# oled_array_v1.net
KiCad netlist of a schematic drawn in EAGLE
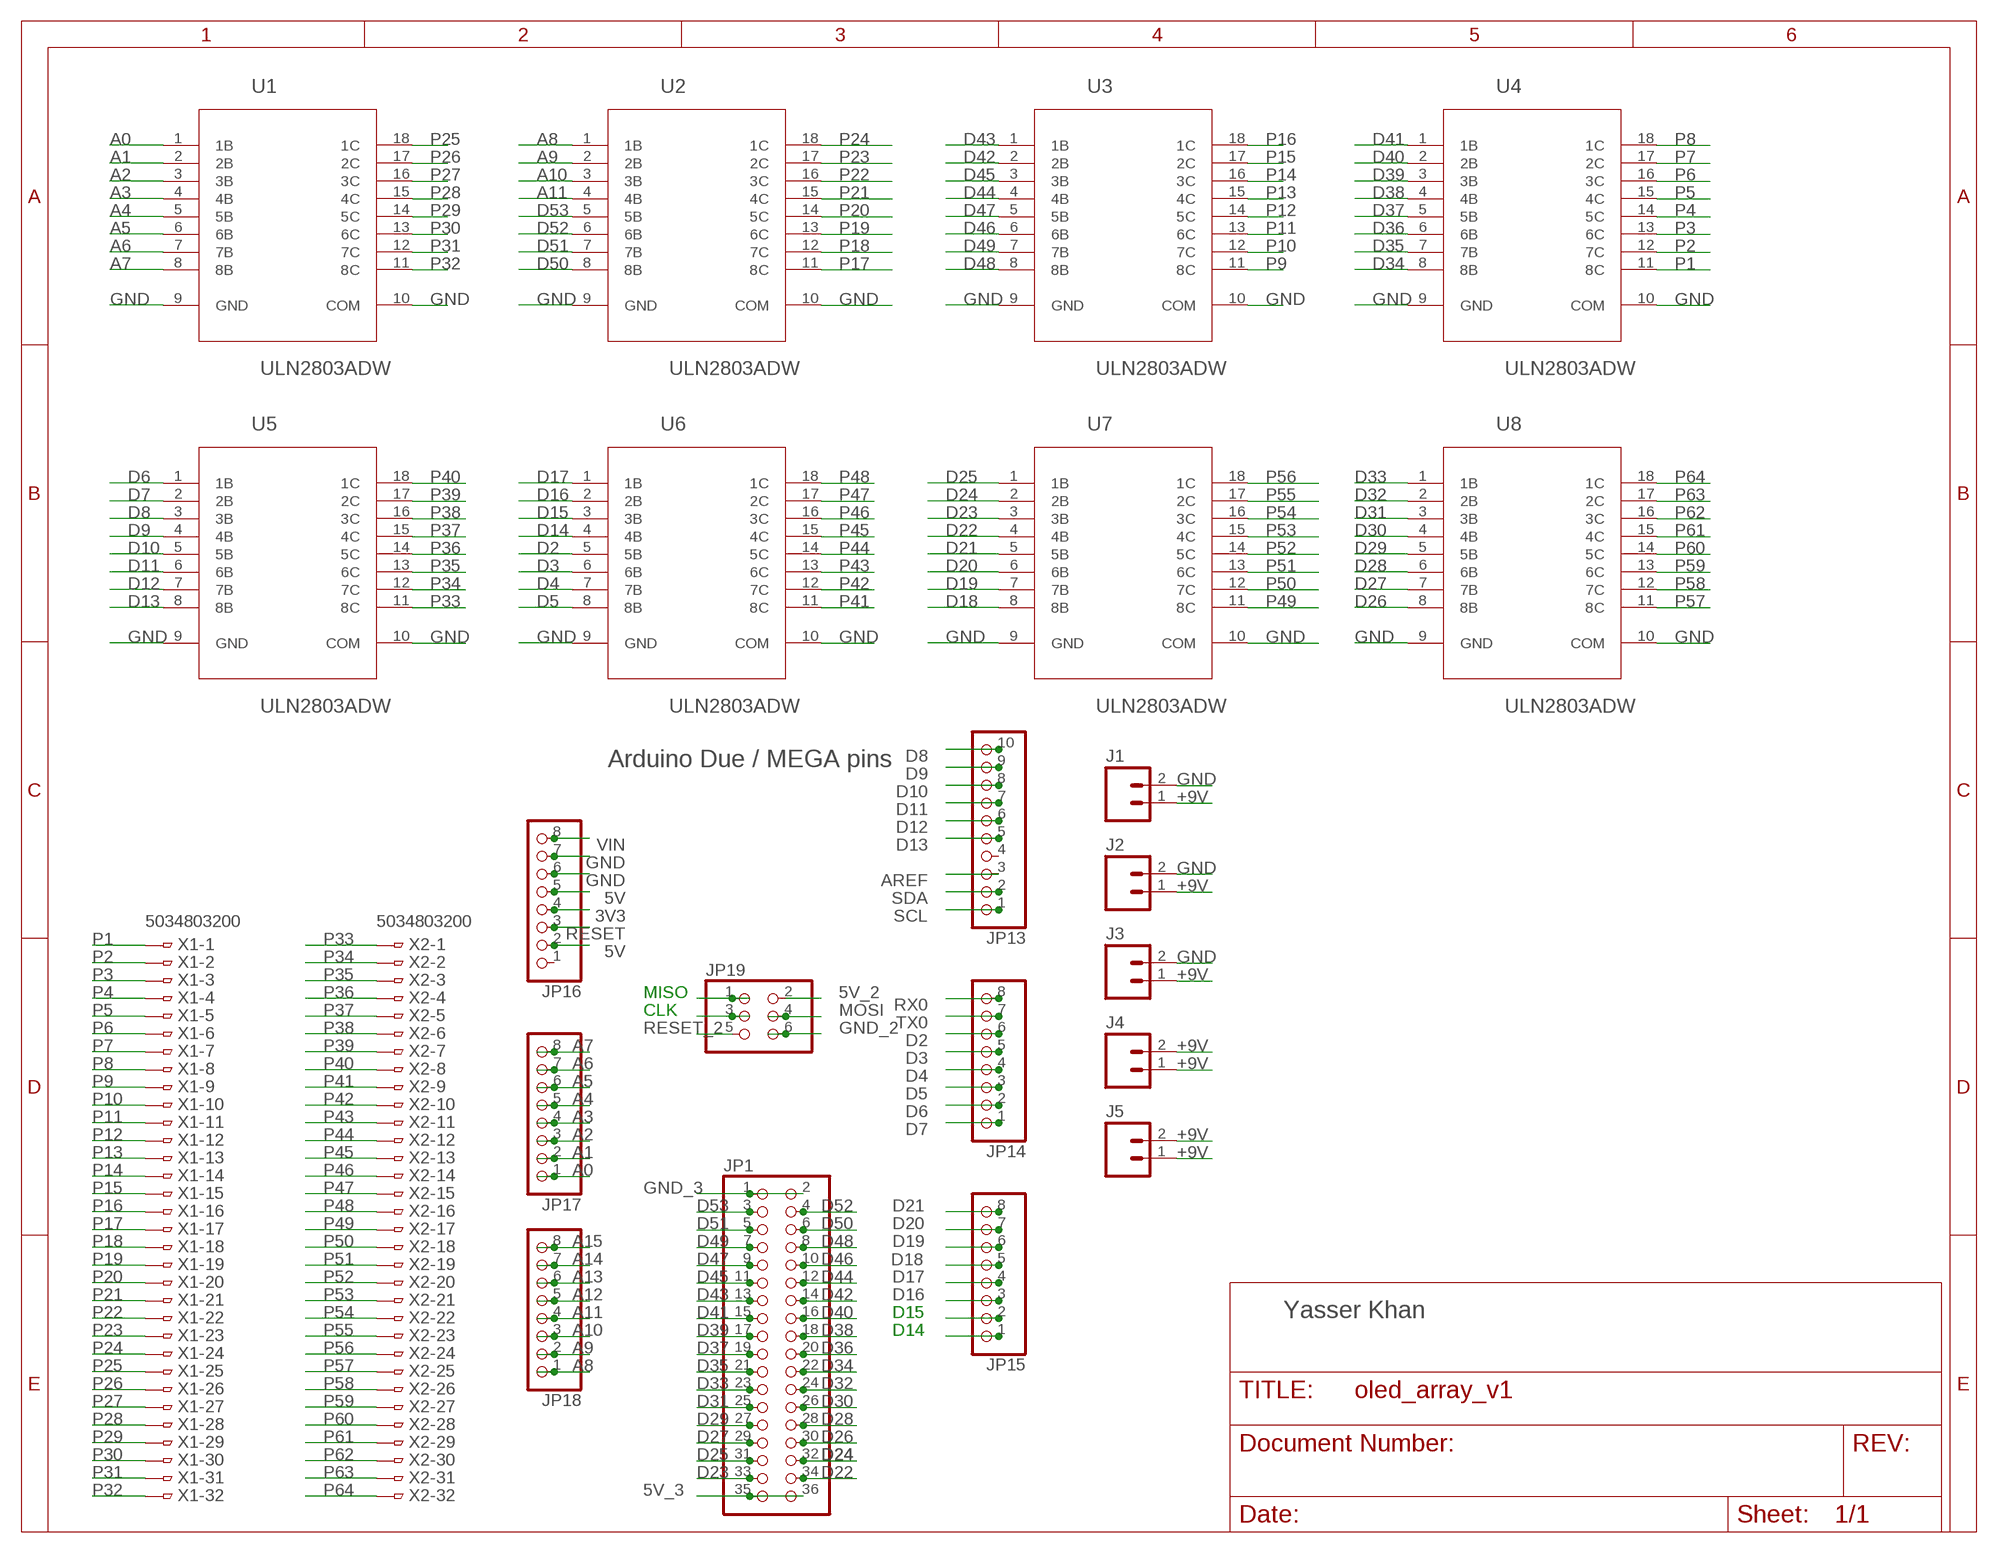
[diagram p0: schematic, sheet 1]

(export (version "E")
  (design (tool "Eeschema 10.0.6"))
  (components
    (comp (ref "J1")
      (value "M02PTH")
      (footprint "eagle-import:1X02")
      (libsource (lib "eagle-import") (part "M02PTH"))
    )
    (comp (ref "J2")
      (value "M02PTH")
      (footprint "eagle-import:1X02")
      (libsource (lib "eagle-import") (part "M02PTH"))
    )
    (comp (ref "J3")
      (value "M02PTH")
      (footprint "eagle-import:1X02")
      (libsource (lib "eagle-import") (part "M02PTH"))
    )
    (comp (ref "J4")
      (value "M02PTH")
      (footprint "eagle-import:1X02")
      (libsource (lib "eagle-import") (part "M02PTH"))
    )
    (comp (ref "J5")
      (value "M02PTH")
      (footprint "eagle-import:1X02")
      (libsource (lib "eagle-import") (part "M02PTH"))
    )
    (comp (ref "JP1")
      (value "PINHD-2X18")
      (footprint "eagle-import:2X18")
      (libsource (lib "eagle-import") (part "PINHD-2X18"))
    )
    (comp (ref "JP13")
      (value "PINHD-1X10")
      (footprint "eagle-import:1X10")
      (libsource (lib "eagle-import") (part "PINHD-1X10"))
    )
    (comp (ref "JP14")
      (value "PINHD-1X8")
      (footprint "eagle-import:1X08")
      (libsource (lib "eagle-import") (part "PINHD-1X8"))
    )
    (comp (ref "JP15")
      (value "PINHD-1X8")
      (footprint "eagle-import:1X08")
      (libsource (lib "eagle-import") (part "PINHD-1X8"))
    )
    (comp (ref "JP16")
      (value "PINHD-1X8")
      (footprint "eagle-import:1X08")
      (libsource (lib "eagle-import") (part "PINHD-1X8"))
    )
    (comp (ref "JP17")
      (value "PINHD-1X8")
      (footprint "eagle-import:1X08")
      (libsource (lib "eagle-import") (part "PINHD-1X8"))
    )
    (comp (ref "JP18")
      (value "PINHD-1X8")
      (footprint "eagle-import:1X08")
      (libsource (lib "eagle-import") (part "PINHD-1X8"))
    )
    (comp (ref "JP19")
      (value "PINHD-2X3")
      (footprint "eagle-import:2X03")
      (libsource (lib "eagle-import") (part "PINHD-2X3"))
    )
    (comp (ref "U1")
      (value "ULN2803ADW")
      (footprint "eagle-import:SOIC127P1030X265-18N")
      (libsource (lib "eagle-import") (part "ULN2803ADW"))
    )
    (comp (ref "U2")
      (value "ULN2803ADW")
      (footprint "eagle-import:SOIC127P1030X265-18N")
      (libsource (lib "eagle-import") (part "ULN2803ADW"))
    )
    (comp (ref "U3")
      (value "ULN2803ADW")
      (footprint "eagle-import:SOIC127P1030X265-18N")
      (libsource (lib "eagle-import") (part "ULN2803ADW"))
    )
    (comp (ref "U4")
      (value "ULN2803ADW")
      (footprint "eagle-import:SOIC127P1030X265-18N")
      (libsource (lib "eagle-import") (part "ULN2803ADW"))
    )
    (comp (ref "U5")
      (value "ULN2803ADW")
      (footprint "eagle-import:SOIC127P1030X265-18N")
      (libsource (lib "eagle-import") (part "ULN2803ADW"))
    )
    (comp (ref "U6")
      (value "ULN2803ADW")
      (footprint "eagle-import:SOIC127P1030X265-18N")
      (libsource (lib "eagle-import") (part "ULN2803ADW"))
    )
    (comp (ref "U7")
      (value "ULN2803ADW")
      (footprint "eagle-import:SOIC127P1030X265-18N")
      (libsource (lib "eagle-import") (part "ULN2803ADW"))
    )
    (comp (ref "U8")
      (value "ULN2803ADW")
      (footprint "eagle-import:SOIC127P1030X265-18N")
      (libsource (lib "eagle-import") (part "ULN2803ADW"))
    )
    (comp (ref "X1")
      (value "5034803200")
      (footprint "eagle-import:5034803200")
      (libsource (lib "eagle-import") (part "5034803200"))
    )
    (comp (ref "X2")
      (value "5034803200")
      (footprint "eagle-import:5034803200")
      (libsource (lib "eagle-import") (part "5034803200"))
    )
  )
  (nets
    (net (code "1") (name "/+9V") (class "Default")
      (node (ref "J1") (pin "1") (pinfunction "1_1") (pintype "passive"))
      (node (ref "J2") (pin "1") (pinfunction "1_1") (pintype "passive"))
      (node (ref "J3") (pin "1") (pinfunction "1_1") (pintype "passive"))
      (node (ref "J4") (pin "1") (pinfunction "1_1") (pintype "passive"))
      (node (ref "J4") (pin "2") (pinfunction "2_2") (pintype "passive"))
      (node (ref "J5") (pin "1") (pinfunction "1_1") (pintype "passive"))
      (node (ref "J5") (pin "2") (pinfunction "2_2") (pintype "passive"))
    )
    (net (code "2") (name "/3V3") (class "Default")
      (node (ref "JP16") (pin "4") (pinfunction "4_4") (pintype "passive"))
    )
    (net (code "3") (name "/5V") (class "Default")
      (node (ref "JP16") (pin "2") (pinfunction "2_2") (pintype "passive"))
      (node (ref "JP16") (pin "5") (pinfunction "5_5") (pintype "passive"))
    )
    (net (code "4") (name "/5V_2") (class "Default")
      (node (ref "JP19") (pin "2") (pinfunction "2_2") (pintype "passive"))
    )
    (net (code "5") (name "/5V_3") (class "Default")
      (node (ref "JP1") (pin "35") (pinfunction "35_35") (pintype "passive"))
      (node (ref "JP1") (pin "36") (pinfunction "36_36") (pintype "passive"))
    )
    (net (code "6") (name "/A0") (class "Default")
      (node (ref "JP17") (pin "1") (pinfunction "1_1") (pintype "passive"))
      (node (ref "U1") (pin "1") (pinfunction "1B_1") (pintype "input"))
    )
    (net (code "7") (name "/A1") (class "Default")
      (node (ref "JP17") (pin "2") (pinfunction "2_2") (pintype "passive"))
      (node (ref "U1") (pin "2") (pinfunction "2B_2") (pintype "input"))
    )
    (net (code "8") (name "/A2") (class "Default")
      (node (ref "JP17") (pin "3") (pinfunction "3_3") (pintype "passive"))
      (node (ref "U1") (pin "3") (pinfunction "3B_3") (pintype "input"))
    )
    (net (code "9") (name "/A3") (class "Default")
      (node (ref "JP17") (pin "4") (pinfunction "4_4") (pintype "passive"))
      (node (ref "U1") (pin "4") (pinfunction "4B_4") (pintype "input"))
    )
    (net (code "10") (name "/A4") (class "Default")
      (node (ref "JP17") (pin "5") (pinfunction "5_5") (pintype "passive"))
      (node (ref "U1") (pin "5") (pinfunction "5B_5") (pintype "input"))
    )
    (net (code "11") (name "/A5") (class "Default")
      (node (ref "JP17") (pin "6") (pinfunction "6_6") (pintype "passive"))
      (node (ref "U1") (pin "6") (pinfunction "6B_6") (pintype "input"))
    )
    (net (code "12") (name "/A6") (class "Default")
      (node (ref "JP17") (pin "7") (pinfunction "7_7") (pintype "passive"))
      (node (ref "U1") (pin "7") (pinfunction "7B_7") (pintype "input"))
    )
    (net (code "13") (name "/A7") (class "Default")
      (node (ref "JP17") (pin "8") (pinfunction "8_8") (pintype "passive"))
      (node (ref "U1") (pin "8") (pinfunction "8B_8") (pintype "input"))
    )
    (net (code "14") (name "/A8") (class "Default")
      (node (ref "JP18") (pin "1") (pinfunction "1_1") (pintype "passive"))
      (node (ref "U2") (pin "1") (pinfunction "1B_1") (pintype "input"))
    )
    (net (code "15") (name "/A9") (class "Default")
      (node (ref "JP18") (pin "2") (pinfunction "2_2") (pintype "passive"))
      (node (ref "U2") (pin "2") (pinfunction "2B_2") (pintype "input"))
    )
    (net (code "16") (name "/A10") (class "Default")
      (node (ref "JP18") (pin "3") (pinfunction "3_3") (pintype "passive"))
      (node (ref "U2") (pin "3") (pinfunction "3B_3") (pintype "input"))
    )
    (net (code "17") (name "/A11") (class "Default")
      (node (ref "JP18") (pin "4") (pinfunction "4_4") (pintype "passive"))
      (node (ref "U2") (pin "4") (pinfunction "4B_4") (pintype "input"))
    )
    (net (code "18") (name "/A12") (class "Default")
      (node (ref "JP18") (pin "5") (pinfunction "5_5") (pintype "passive"))
    )
    (net (code "19") (name "/A13") (class "Default")
      (node (ref "JP18") (pin "6") (pinfunction "6_6") (pintype "passive"))
    )
    (net (code "20") (name "/A14") (class "Default")
      (node (ref "JP18") (pin "7") (pinfunction "7_7") (pintype "passive"))
    )
    (net (code "21") (name "/A15") (class "Default")
      (node (ref "JP18") (pin "8") (pinfunction "8_8") (pintype "passive"))
    )
    (net (code "22") (name "/AREF") (class "Default")
      (node (ref "JP13") (pin "3") (pinfunction "3_3") (pintype "passive"))
    )
    (net (code "23") (name "/CLK") (class "Default")
      (node (ref "JP19") (pin "3") (pinfunction "3_3") (pintype "passive"))
    )
    (net (code "24") (name "/D2") (class "Default")
      (node (ref "JP14") (pin "6") (pinfunction "6_6") (pintype "passive"))
      (node (ref "U6") (pin "5") (pinfunction "5B_5") (pintype "input"))
    )
    (net (code "25") (name "/D3") (class "Default")
      (node (ref "JP14") (pin "5") (pinfunction "5_5") (pintype "passive"))
      (node (ref "U6") (pin "6") (pinfunction "6B_6") (pintype "input"))
    )
    (net (code "26") (name "/D4") (class "Default")
      (node (ref "JP14") (pin "4") (pinfunction "4_4") (pintype "passive"))
      (node (ref "U6") (pin "7") (pinfunction "7B_7") (pintype "input"))
    )
    (net (code "27") (name "/D5") (class "Default")
      (node (ref "JP14") (pin "3") (pinfunction "3_3") (pintype "passive"))
      (node (ref "U6") (pin "8") (pinfunction "8B_8") (pintype "input"))
    )
    (net (code "28") (name "/D6") (class "Default")
      (node (ref "JP14") (pin "2") (pinfunction "2_2") (pintype "passive"))
      (node (ref "U5") (pin "1") (pinfunction "1B_1") (pintype "input"))
    )
    (net (code "29") (name "/D7") (class "Default")
      (node (ref "JP14") (pin "1") (pinfunction "1_1") (pintype "passive"))
      (node (ref "U5") (pin "2") (pinfunction "2B_2") (pintype "input"))
    )
    (net (code "30") (name "/D8") (class "Default")
      (node (ref "JP13") (pin "10") (pinfunction "10_10") (pintype "passive"))
      (node (ref "U5") (pin "3") (pinfunction "3B_3") (pintype "input"))
    )
    (net (code "31") (name "/D9") (class "Default")
      (node (ref "JP13") (pin "9") (pinfunction "9_9") (pintype "passive"))
      (node (ref "U5") (pin "4") (pinfunction "4B_4") (pintype "input"))
    )
    (net (code "32") (name "/D10") (class "Default")
      (node (ref "JP13") (pin "8") (pinfunction "8_8") (pintype "passive"))
      (node (ref "U5") (pin "5") (pinfunction "5B_5") (pintype "input"))
    )
    (net (code "33") (name "/D11") (class "Default")
      (node (ref "JP13") (pin "7") (pinfunction "7_7") (pintype "passive"))
      (node (ref "U5") (pin "6") (pinfunction "6B_6") (pintype "input"))
    )
    (net (code "34") (name "/D12") (class "Default")
      (node (ref "JP13") (pin "6") (pinfunction "6_6") (pintype "passive"))
      (node (ref "U5") (pin "7") (pinfunction "7B_7") (pintype "input"))
    )
    (net (code "35") (name "/D13") (class "Default")
      (node (ref "JP13") (pin "5") (pinfunction "5_5") (pintype "passive"))
      (node (ref "U5") (pin "8") (pinfunction "8B_8") (pintype "input"))
    )
    (net (code "36") (name "/D14") (class "Default")
      (node (ref "JP15") (pin "1") (pinfunction "1_1") (pintype "passive"))
      (node (ref "U6") (pin "4") (pinfunction "4B_4") (pintype "input"))
    )
    (net (code "37") (name "/D15") (class "Default")
      (node (ref "JP15") (pin "2") (pinfunction "2_2") (pintype "passive"))
      (node (ref "U6") (pin "3") (pinfunction "3B_3") (pintype "input"))
    )
    (net (code "38") (name "/D16") (class "Default")
      (node (ref "JP15") (pin "3") (pinfunction "3_3") (pintype "passive"))
      (node (ref "U6") (pin "2") (pinfunction "2B_2") (pintype "input"))
    )
    (net (code "39") (name "/D17") (class "Default")
      (node (ref "JP15") (pin "4") (pinfunction "4_4") (pintype "passive"))
      (node (ref "U6") (pin "1") (pinfunction "1B_1") (pintype "input"))
    )
    (net (code "40") (name "/D18") (class "Default")
      (node (ref "JP15") (pin "5") (pinfunction "5_5") (pintype "passive"))
      (node (ref "U7") (pin "8") (pinfunction "8B_8") (pintype "input"))
    )
    (net (code "41") (name "/D19") (class "Default")
      (node (ref "JP15") (pin "6") (pinfunction "6_6") (pintype "passive"))
      (node (ref "U7") (pin "7") (pinfunction "7B_7") (pintype "input"))
    )
    (net (code "42") (name "/D20") (class "Default")
      (node (ref "JP15") (pin "7") (pinfunction "7_7") (pintype "passive"))
      (node (ref "U7") (pin "6") (pinfunction "6B_6") (pintype "input"))
    )
    (net (code "43") (name "/D21") (class "Default")
      (node (ref "JP15") (pin "8") (pinfunction "8_8") (pintype "passive"))
      (node (ref "U7") (pin "5") (pinfunction "5B_5") (pintype "input"))
    )
    (net (code "44") (name "/D22") (class "Default")
      (node (ref "JP1") (pin "34") (pinfunction "34_34") (pintype "passive"))
      (node (ref "U7") (pin "4") (pinfunction "4B_4") (pintype "input"))
    )
    (net (code "45") (name "/D23") (class "Default")
      (node (ref "JP1") (pin "33") (pinfunction "33_33") (pintype "passive"))
      (node (ref "U7") (pin "3") (pinfunction "3B_3") (pintype "input"))
    )
    (net (code "46") (name "/D24") (class "Default")
      (node (ref "JP1") (pin "32") (pinfunction "32_32") (pintype "passive"))
      (node (ref "U7") (pin "2") (pinfunction "2B_2") (pintype "input"))
    )
    (net (code "47") (name "/D25") (class "Default")
      (node (ref "JP1") (pin "31") (pinfunction "31_31") (pintype "passive"))
      (node (ref "U7") (pin "1") (pinfunction "1B_1") (pintype "input"))
    )
    (net (code "48") (name "/D26") (class "Default")
      (node (ref "JP1") (pin "30") (pinfunction "30_30") (pintype "passive"))
      (node (ref "U8") (pin "8") (pinfunction "8B_8") (pintype "input"))
    )
    (net (code "49") (name "/D27") (class "Default")
      (node (ref "JP1") (pin "29") (pinfunction "29_29") (pintype "passive"))
      (node (ref "U8") (pin "7") (pinfunction "7B_7") (pintype "input"))
    )
    (net (code "50") (name "/D28") (class "Default")
      (node (ref "JP1") (pin "28") (pinfunction "28_28") (pintype "passive"))
      (node (ref "U8") (pin "6") (pinfunction "6B_6") (pintype "input"))
    )
    (net (code "51") (name "/D29") (class "Default")
      (node (ref "JP1") (pin "27") (pinfunction "27_27") (pintype "passive"))
      (node (ref "U8") (pin "5") (pinfunction "5B_5") (pintype "input"))
    )
    (net (code "52") (name "/D30") (class "Default")
      (node (ref "JP1") (pin "26") (pinfunction "26_26") (pintype "passive"))
      (node (ref "U8") (pin "4") (pinfunction "4B_4") (pintype "input"))
    )
    (net (code "53") (name "/D31") (class "Default")
      (node (ref "JP1") (pin "25") (pinfunction "25_25") (pintype "passive"))
      (node (ref "U8") (pin "3") (pinfunction "3B_3") (pintype "input"))
    )
    (net (code "54") (name "/D32") (class "Default")
      (node (ref "JP1") (pin "24") (pinfunction "24_24") (pintype "passive"))
      (node (ref "U8") (pin "2") (pinfunction "2B_2") (pintype "input"))
    )
    (net (code "55") (name "/D33") (class "Default")
      (node (ref "JP1") (pin "23") (pinfunction "23_23") (pintype "passive"))
      (node (ref "U8") (pin "1") (pinfunction "1B_1") (pintype "input"))
    )
    (net (code "56") (name "/D34") (class "Default")
      (node (ref "JP1") (pin "22") (pinfunction "22_22") (pintype "passive"))
      (node (ref "U4") (pin "8") (pinfunction "8B_8") (pintype "input"))
    )
    (net (code "57") (name "/D35") (class "Default")
      (node (ref "JP1") (pin "21") (pinfunction "21_21") (pintype "passive"))
      (node (ref "U4") (pin "7") (pinfunction "7B_7") (pintype "input"))
    )
    (net (code "58") (name "/D36") (class "Default")
      (node (ref "JP1") (pin "20") (pinfunction "20_20") (pintype "passive"))
      (node (ref "U4") (pin "6") (pinfunction "6B_6") (pintype "input"))
    )
    (net (code "59") (name "/D37") (class "Default")
      (node (ref "JP1") (pin "19") (pinfunction "19_19") (pintype "passive"))
      (node (ref "U4") (pin "5") (pinfunction "5B_5") (pintype "input"))
    )
    (net (code "60") (name "/D38") (class "Default")
      (node (ref "JP1") (pin "18") (pinfunction "18_18") (pintype "passive"))
      (node (ref "U4") (pin "4") (pinfunction "4B_4") (pintype "input"))
    )
    (net (code "61") (name "/D39") (class "Default")
      (node (ref "JP1") (pin "17") (pinfunction "17_17") (pintype "passive"))
      (node (ref "U4") (pin "3") (pinfunction "3B_3") (pintype "input"))
    )
    (net (code "62") (name "/D40") (class "Default")
      (node (ref "JP1") (pin "16") (pinfunction "16_16") (pintype "passive"))
      (node (ref "U4") (pin "2") (pinfunction "2B_2") (pintype "input"))
    )
    (net (code "63") (name "/D41") (class "Default")
      (node (ref "JP1") (pin "15") (pinfunction "15_15") (pintype "passive"))
      (node (ref "U4") (pin "1") (pinfunction "1B_1") (pintype "input"))
    )
    (net (code "64") (name "/D42") (class "Default")
      (node (ref "JP1") (pin "14") (pinfunction "14_14") (pintype "passive"))
      (node (ref "U3") (pin "2") (pinfunction "2B_2") (pintype "input"))
    )
    (net (code "65") (name "/D43") (class "Default")
      (node (ref "JP1") (pin "13") (pinfunction "13_13") (pintype "passive"))
      (node (ref "U3") (pin "1") (pinfunction "1B_1") (pintype "input"))
    )
    (net (code "66") (name "/D44") (class "Default")
      (node (ref "JP1") (pin "12") (pinfunction "12_12") (pintype "passive"))
      (node (ref "U3") (pin "4") (pinfunction "4B_4") (pintype "input"))
    )
    (net (code "67") (name "/D45") (class "Default")
      (node (ref "JP1") (pin "11") (pinfunction "11_11") (pintype "passive"))
      (node (ref "U3") (pin "3") (pinfunction "3B_3") (pintype "input"))
    )
    (net (code "68") (name "/D46") (class "Default")
      (node (ref "JP1") (pin "10") (pinfunction "10_10") (pintype "passive"))
      (node (ref "U3") (pin "6") (pinfunction "6B_6") (pintype "input"))
    )
    (net (code "69") (name "/D47") (class "Default")
      (node (ref "JP1") (pin "9") (pinfunction "9_9") (pintype "passive"))
      (node (ref "U3") (pin "5") (pinfunction "5B_5") (pintype "input"))
    )
    (net (code "70") (name "/D48") (class "Default")
      (node (ref "JP1") (pin "8") (pinfunction "8_8") (pintype "passive"))
      (node (ref "U3") (pin "8") (pinfunction "8B_8") (pintype "input"))
    )
    (net (code "71") (name "/D49") (class "Default")
      (node (ref "JP1") (pin "7") (pinfunction "7_7") (pintype "passive"))
      (node (ref "U3") (pin "7") (pinfunction "7B_7") (pintype "input"))
    )
    (net (code "72") (name "/D50") (class "Default")
      (node (ref "JP1") (pin "6") (pinfunction "6_6") (pintype "passive"))
      (node (ref "U2") (pin "8") (pinfunction "8B_8") (pintype "input"))
    )
    (net (code "73") (name "/D51") (class "Default")
      (node (ref "JP1") (pin "5") (pinfunction "5_5") (pintype "passive"))
      (node (ref "U2") (pin "7") (pinfunction "7B_7") (pintype "input"))
    )
    (net (code "74") (name "/D52") (class "Default")
      (node (ref "JP1") (pin "4") (pinfunction "4_4") (pintype "passive"))
      (node (ref "U2") (pin "6") (pinfunction "6B_6") (pintype "input"))
    )
    (net (code "75") (name "/D53") (class "Default")
      (node (ref "JP1") (pin "3") (pinfunction "3_3") (pintype "passive"))
      (node (ref "U2") (pin "5") (pinfunction "5B_5") (pintype "input"))
    )
    (net (code "76") (name "/GND") (class "Default")
      (node (ref "J1") (pin "2") (pinfunction "2_2") (pintype "passive"))
      (node (ref "J2") (pin "2") (pinfunction "2_2") (pintype "passive"))
      (node (ref "J3") (pin "2") (pinfunction "2_2") (pintype "passive"))
      (node (ref "JP16") (pin "6") (pinfunction "6_6") (pintype "passive"))
      (node (ref "JP16") (pin "7") (pinfunction "7_7") (pintype "passive"))
      (node (ref "U1") (pin "10") (pinfunction "COM_10") (pintype "output"))
      (node (ref "U1") (pin "9") (pinfunction "GND_9") (pintype "passive"))
      (node (ref "U2") (pin "10") (pinfunction "COM_10") (pintype "output"))
      (node (ref "U2") (pin "9") (pinfunction "GND_9") (pintype "passive"))
      (node (ref "U3") (pin "10") (pinfunction "COM_10") (pintype "output"))
      (node (ref "U3") (pin "9") (pinfunction "GND_9") (pintype "passive"))
      (node (ref "U4") (pin "10") (pinfunction "COM_10") (pintype "output"))
      (node (ref "U4") (pin "9") (pinfunction "GND_9") (pintype "passive"))
      (node (ref "U5") (pin "10") (pinfunction "COM_10") (pintype "output"))
      (node (ref "U5") (pin "9") (pinfunction "GND_9") (pintype "passive"))
      (node (ref "U6") (pin "10") (pinfunction "COM_10") (pintype "output"))
      (node (ref "U6") (pin "9") (pinfunction "GND_9") (pintype "passive"))
      (node (ref "U7") (pin "10") (pinfunction "COM_10") (pintype "output"))
      (node (ref "U7") (pin "9") (pinfunction "GND_9") (pintype "passive"))
      (node (ref "U8") (pin "10") (pinfunction "COM_10") (pintype "output"))
      (node (ref "U8") (pin "9") (pinfunction "GND_9") (pintype "passive"))
    )
    (net (code "77") (name "/GND_2") (class "Default")
      (node (ref "JP19") (pin "6") (pinfunction "6_6") (pintype "passive"))
    )
    (net (code "78") (name "/GND_3") (class "Default")
      (node (ref "JP1") (pin "1") (pinfunction "1_1") (pintype "passive"))
      (node (ref "JP1") (pin "2") (pinfunction "2_2") (pintype "passive"))
    )
    (net (code "79") (name "/MISO") (class "Default")
      (node (ref "JP19") (pin "1") (pinfunction "1_1") (pintype "passive"))
    )
    (net (code "80") (name "/MOSI") (class "Default")
      (node (ref "JP19") (pin "4") (pinfunction "4_4") (pintype "passive"))
    )
    (net (code "81") (name "/P1") (class "Default")
      (node (ref "U4") (pin "11") (pinfunction "8C_11") (pintype "output"))
      (node (ref "X1") (pin "1") (pinfunction "1_1") (pintype "passive"))
    )
    (net (code "82") (name "/P2") (class "Default")
      (node (ref "U4") (pin "12") (pinfunction "7C_12") (pintype "output"))
      (node (ref "X1") (pin "2") (pinfunction "1_2") (pintype "passive"))
    )
    (net (code "83") (name "/P3") (class "Default")
      (node (ref "U4") (pin "13") (pinfunction "6C_13") (pintype "output"))
      (node (ref "X1") (pin "3") (pinfunction "1_3") (pintype "passive"))
    )
    (net (code "84") (name "/P4") (class "Default")
      (node (ref "U4") (pin "14") (pinfunction "5C_14") (pintype "output"))
      (node (ref "X1") (pin "4") (pinfunction "1_4") (pintype "passive"))
    )
    (net (code "85") (name "/P5") (class "Default")
      (node (ref "U4") (pin "15") (pinfunction "4C_15") (pintype "output"))
      (node (ref "X1") (pin "5") (pinfunction "1_5") (pintype "passive"))
    )
    (net (code "86") (name "/P6") (class "Default")
      (node (ref "U4") (pin "16") (pinfunction "3C_16") (pintype "output"))
      (node (ref "X1") (pin "6") (pinfunction "1_6") (pintype "passive"))
    )
    (net (code "87") (name "/P7") (class "Default")
      (node (ref "U4") (pin "17") (pinfunction "2C_17") (pintype "output"))
      (node (ref "X1") (pin "7") (pinfunction "1_7") (pintype "passive"))
    )
    (net (code "88") (name "/P8") (class "Default")
      (node (ref "U4") (pin "18") (pinfunction "1C_18") (pintype "output"))
      (node (ref "X1") (pin "8") (pinfunction "1_8") (pintype "passive"))
    )
    (net (code "89") (name "/P9") (class "Default")
      (node (ref "U3") (pin "11") (pinfunction "8C_11") (pintype "output"))
      (node (ref "X1") (pin "9") (pinfunction "1_9") (pintype "passive"))
    )
    (net (code "90") (name "/P10") (class "Default")
      (node (ref "U3") (pin "12") (pinfunction "7C_12") (pintype "output"))
      (node (ref "X1") (pin "10") (pinfunction "1_10") (pintype "passive"))
    )
    (net (code "91") (name "/P11") (class "Default")
      (node (ref "U3") (pin "13") (pinfunction "6C_13") (pintype "output"))
      (node (ref "X1") (pin "11") (pinfunction "1_11") (pintype "passive"))
    )
    (net (code "92") (name "/P12") (class "Default")
      (node (ref "U3") (pin "14") (pinfunction "5C_14") (pintype "output"))
      (node (ref "X1") (pin "12") (pinfunction "1_12") (pintype "passive"))
    )
    (net (code "93") (name "/P13") (class "Default")
      (node (ref "U3") (pin "15") (pinfunction "4C_15") (pintype "output"))
      (node (ref "X1") (pin "13") (pinfunction "1_13") (pintype "passive"))
    )
    (net (code "94") (name "/P14") (class "Default")
      (node (ref "U3") (pin "16") (pinfunction "3C_16") (pintype "output"))
      (node (ref "X1") (pin "14") (pinfunction "1_14") (pintype "passive"))
    )
    (net (code "95") (name "/P15") (class "Default")
      (node (ref "U3") (pin "17") (pinfunction "2C_17") (pintype "output"))
      (node (ref "X1") (pin "15") (pinfunction "1_15") (pintype "passive"))
    )
    (net (code "96") (name "/P16") (class "Default")
      (node (ref "U3") (pin "18") (pinfunction "1C_18") (pintype "output"))
      (node (ref "X1") (pin "16") (pinfunction "1_16") (pintype "passive"))
    )
    (net (code "97") (name "/P17") (class "Default")
      (node (ref "U2") (pin "11") (pinfunction "8C_11") (pintype "output"))
      (node (ref "X1") (pin "17") (pinfunction "1_17") (pintype "passive"))
    )
    (net (code "98") (name "/P18") (class "Default")
      (node (ref "U2") (pin "12") (pinfunction "7C_12") (pintype "output"))
      (node (ref "X1") (pin "18") (pinfunction "1_18") (pintype "passive"))
    )
    (net (code "99") (name "/P19") (class "Default")
      (node (ref "U2") (pin "13") (pinfunction "6C_13") (pintype "output"))
      (node (ref "X1") (pin "19") (pinfunction "1_19") (pintype "passive"))
    )
    (net (code "100") (name "/P20") (class "Default")
      (node (ref "U2") (pin "14") (pinfunction "5C_14") (pintype "output"))
      (node (ref "X1") (pin "20") (pinfunction "1_20") (pintype "passive"))
    )
    (net (code "101") (name "/P21") (class "Default")
      (node (ref "U2") (pin "15") (pinfunction "4C_15") (pintype "output"))
      (node (ref "X1") (pin "21") (pinfunction "1_21") (pintype "passive"))
    )
    (net (code "102") (name "/P22") (class "Default")
      (node (ref "U2") (pin "16") (pinfunction "3C_16") (pintype "output"))
      (node (ref "X1") (pin "22") (pinfunction "1_22") (pintype "passive"))
    )
    (net (code "103") (name "/P23") (class "Default")
      (node (ref "U2") (pin "17") (pinfunction "2C_17") (pintype "output"))
      (node (ref "X1") (pin "23") (pinfunction "1_23") (pintype "passive"))
    )
    (net (code "104") (name "/P24") (class "Default")
      (node (ref "U2") (pin "18") (pinfunction "1C_18") (pintype "output"))
      (node (ref "X1") (pin "24") (pinfunction "1_24") (pintype "passive"))
    )
    (net (code "105") (name "/P25") (class "Default")
      (node (ref "U1") (pin "18") (pinfunction "1C_18") (pintype "output"))
      (node (ref "X1") (pin "25") (pinfunction "1_25") (pintype "passive"))
    )
    (net (code "106") (name "/P26") (class "Default")
      (node (ref "U1") (pin "17") (pinfunction "2C_17") (pintype "output"))
      (node (ref "X1") (pin "26") (pinfunction "1_26") (pintype "passive"))
    )
    (net (code "107") (name "/P27") (class "Default")
      (node (ref "U1") (pin "16") (pinfunction "3C_16") (pintype "output"))
      (node (ref "X1") (pin "27") (pinfunction "1_27") (pintype "passive"))
    )
    (net (code "108") (name "/P28") (class "Default")
      (node (ref "U1") (pin "15") (pinfunction "4C_15") (pintype "output"))
      (node (ref "X1") (pin "28") (pinfunction "1_28") (pintype "passive"))
    )
    (net (code "109") (name "/P29") (class "Default")
      (node (ref "U1") (pin "14") (pinfunction "5C_14") (pintype "output"))
      (node (ref "X1") (pin "29") (pinfunction "1_29") (pintype "passive"))
    )
    (net (code "110") (name "/P30") (class "Default")
      (node (ref "U1") (pin "13") (pinfunction "6C_13") (pintype "output"))
      (node (ref "X1") (pin "30") (pinfunction "1_30") (pintype "passive"))
    )
    (net (code "111") (name "/P31") (class "Default")
      (node (ref "U1") (pin "12") (pinfunction "7C_12") (pintype "output"))
      (node (ref "X1") (pin "31") (pinfunction "1_31") (pintype "passive"))
    )
    (net (code "112") (name "/P32") (class "Default")
      (node (ref "U1") (pin "11") (pinfunction "8C_11") (pintype "output"))
      (node (ref "X1") (pin "32") (pinfunction "1_32") (pintype "passive"))
    )
    (net (code "113") (name "/P33") (class "Default")
      (node (ref "U5") (pin "11") (pinfunction "8C_11") (pintype "output"))
      (node (ref "X2") (pin "1") (pinfunction "1_1") (pintype "passive"))
    )
    (net (code "114") (name "/P34") (class "Default")
      (node (ref "U5") (pin "12") (pinfunction "7C_12") (pintype "output"))
      (node (ref "X2") (pin "2") (pinfunction "1_2") (pintype "passive"))
    )
    (net (code "115") (name "/P35") (class "Default")
      (node (ref "U5") (pin "13") (pinfunction "6C_13") (pintype "output"))
      (node (ref "X2") (pin "3") (pinfunction "1_3") (pintype "passive"))
    )
    (net (code "116") (name "/P36") (class "Default")
      (node (ref "U5") (pin "14") (pinfunction "5C_14") (pintype "output"))
      (node (ref "X2") (pin "4") (pinfunction "1_4") (pintype "passive"))
    )
    (net (code "117") (name "/P37") (class "Default")
      (node (ref "U5") (pin "15") (pinfunction "4C_15") (pintype "output"))
      (node (ref "X2") (pin "5") (pinfunction "1_5") (pintype "passive"))
    )
    (net (code "118") (name "/P38") (class "Default")
      (node (ref "U5") (pin "16") (pinfunction "3C_16") (pintype "output"))
      (node (ref "X2") (pin "6") (pinfunction "1_6") (pintype "passive"))
    )
    (net (code "119") (name "/P39") (class "Default")
      (node (ref "U5") (pin "17") (pinfunction "2C_17") (pintype "output"))
      (node (ref "X2") (pin "7") (pinfunction "1_7") (pintype "passive"))
    )
    (net (code "120") (name "/P40") (class "Default")
      (node (ref "U5") (pin "18") (pinfunction "1C_18") (pintype "output"))
      (node (ref "X2") (pin "8") (pinfunction "1_8") (pintype "passive"))
    )
    (net (code "121") (name "/P41") (class "Default")
      (node (ref "U6") (pin "11") (pinfunction "8C_11") (pintype "output"))
      (node (ref "X2") (pin "9") (pinfunction "1_9") (pintype "passive"))
    )
    (net (code "122") (name "/P42") (class "Default")
      (node (ref "U6") (pin "12") (pinfunction "7C_12") (pintype "output"))
      (node (ref "X2") (pin "10") (pinfunction "1_10") (pintype "passive"))
    )
    (net (code "123") (name "/P43") (class "Default")
      (node (ref "U6") (pin "13") (pinfunction "6C_13") (pintype "output"))
      (node (ref "X2") (pin "11") (pinfunction "1_11") (pintype "passive"))
    )
    (net (code "124") (name "/P44") (class "Default")
      (node (ref "U6") (pin "14") (pinfunction "5C_14") (pintype "output"))
      (node (ref "X2") (pin "12") (pinfunction "1_12") (pintype "passive"))
    )
    (net (code "125") (name "/P45") (class "Default")
      (node (ref "U6") (pin "15") (pinfunction "4C_15") (pintype "output"))
      (node (ref "X2") (pin "13") (pinfunction "1_13") (pintype "passive"))
    )
    (net (code "126") (name "/P46") (class "Default")
      (node (ref "U6") (pin "16") (pinfunction "3C_16") (pintype "output"))
      (node (ref "X2") (pin "14") (pinfunction "1_14") (pintype "passive"))
    )
    (net (code "127") (name "/P47") (class "Default")
      (node (ref "U6") (pin "17") (pinfunction "2C_17") (pintype "output"))
      (node (ref "X2") (pin "15") (pinfunction "1_15") (pintype "passive"))
    )
    (net (code "128") (name "/P48") (class "Default")
      (node (ref "U6") (pin "18") (pinfunction "1C_18") (pintype "output"))
      (node (ref "X2") (pin "16") (pinfunction "1_16") (pintype "passive"))
    )
    (net (code "129") (name "/P49") (class "Default")
      (node (ref "U7") (pin "11") (pinfunction "8C_11") (pintype "output"))
      (node (ref "X2") (pin "17") (pinfunction "1_17") (pintype "passive"))
    )
    (net (code "130") (name "/P50") (class "Default")
      (node (ref "U7") (pin "12") (pinfunction "7C_12") (pintype "output"))
      (node (ref "X2") (pin "18") (pinfunction "1_18") (pintype "passive"))
    )
    (net (code "131") (name "/P51") (class "Default")
      (node (ref "U7") (pin "13") (pinfunction "6C_13") (pintype "output"))
      (node (ref "X2") (pin "19") (pinfunction "1_19") (pintype "passive"))
    )
    (net (code "132") (name "/P52") (class "Default")
      (node (ref "U7") (pin "14") (pinfunction "5C_14") (pintype "output"))
      (node (ref "X2") (pin "20") (pinfunction "1_20") (pintype "passive"))
    )
    (net (code "133") (name "/P53") (class "Default")
      (node (ref "U7") (pin "15") (pinfunction "4C_15") (pintype "output"))
      (node (ref "X2") (pin "21") (pinfunction "1_21") (pintype "passive"))
    )
    (net (code "134") (name "/P54") (class "Default")
      (node (ref "U7") (pin "16") (pinfunction "3C_16") (pintype "output"))
      (node (ref "X2") (pin "22") (pinfunction "1_22") (pintype "passive"))
    )
    (net (code "135") (name "/P55") (class "Default")
      (node (ref "U7") (pin "17") (pinfunction "2C_17") (pintype "output"))
      (node (ref "X2") (pin "23") (pinfunction "1_23") (pintype "passive"))
    )
    (net (code "136") (name "/P56") (class "Default")
      (node (ref "U7") (pin "18") (pinfunction "1C_18") (pintype "output"))
      (node (ref "X2") (pin "24") (pinfunction "1_24") (pintype "passive"))
    )
    (net (code "137") (name "/P57") (class "Default")
      (node (ref "U8") (pin "11") (pinfunction "8C_11") (pintype "output"))
      (node (ref "X2") (pin "25") (pinfunction "1_25") (pintype "passive"))
    )
    (net (code "138") (name "/P58") (class "Default")
      (node (ref "U8") (pin "12") (pinfunction "7C_12") (pintype "output"))
      (node (ref "X2") (pin "26") (pinfunction "1_26") (pintype "passive"))
    )
    (net (code "139") (name "/P59") (class "Default")
      (node (ref "U8") (pin "13") (pinfunction "6C_13") (pintype "output"))
      (node (ref "X2") (pin "27") (pinfunction "1_27") (pintype "passive"))
    )
    (net (code "140") (name "/P60") (class "Default")
      (node (ref "U8") (pin "14") (pinfunction "5C_14") (pintype "output"))
      (node (ref "X2") (pin "28") (pinfunction "1_28") (pintype "passive"))
    )
    (net (code "141") (name "/P61") (class "Default")
      (node (ref "U8") (pin "15") (pinfunction "4C_15") (pintype "output"))
      (node (ref "X2") (pin "29") (pinfunction "1_29") (pintype "passive"))
    )
    (net (code "142") (name "/P62") (class "Default")
      (node (ref "U8") (pin "16") (pinfunction "3C_16") (pintype "output"))
      (node (ref "X2") (pin "30") (pinfunction "1_30") (pintype "passive"))
    )
    (net (code "143") (name "/P63") (class "Default")
      (node (ref "U8") (pin "17") (pinfunction "2C_17") (pintype "output"))
      (node (ref "X2") (pin "31") (pinfunction "1_31") (pintype "passive"))
    )
    (net (code "144") (name "/P64") (class "Default")
      (node (ref "U8") (pin "18") (pinfunction "1C_18") (pintype "output"))
      (node (ref "X2") (pin "32") (pinfunction "1_32") (pintype "passive"))
    )
    (net (code "145") (name "/RESET") (class "Default")
      (node (ref "JP16") (pin "3") (pinfunction "3_3") (pintype "passive"))
    )
    (net (code "146") (name "/RESET_2") (class "Default")
      (node (ref "JP19") (pin "5") (pinfunction "5_5") (pintype "passive"))
    )
    (net (code "147") (name "/RX0") (class "Default")
      (node (ref "JP14") (pin "8") (pinfunction "8_8") (pintype "passive"))
    )
    (net (code "148") (name "/SCL") (class "Default")
      (node (ref "JP13") (pin "1") (pinfunction "1_1") (pintype "passive"))
    )
    (net (code "149") (name "/SDA") (class "Default")
      (node (ref "JP13") (pin "2") (pinfunction "2_2") (pintype "passive"))
    )
    (net (code "150") (name "/TX0") (class "Default")
      (node (ref "JP14") (pin "7") (pinfunction "7_7") (pintype "passive"))
    )
    (net (code "151") (name "/VIN") (class "Default")
      (node (ref "JP16") (pin "8") (pinfunction "8_8") (pintype "passive"))
    )
    (net (code "152") (name "unconnected-(JP13-Pad4)") (class "Default")
      (node (ref "JP13") (pin "4") (pinfunction "4_4") (pintype "passive"))
    )
    (net (code "153") (name "unconnected-(JP16-Pad1)") (class "Default")
      (node (ref "JP16") (pin "1") (pinfunction "1_1") (pintype "passive"))
    )
  )
)
